# LP-IMP-P1_V3.net
KiCad netlist of a schematic drawn in EAGLE
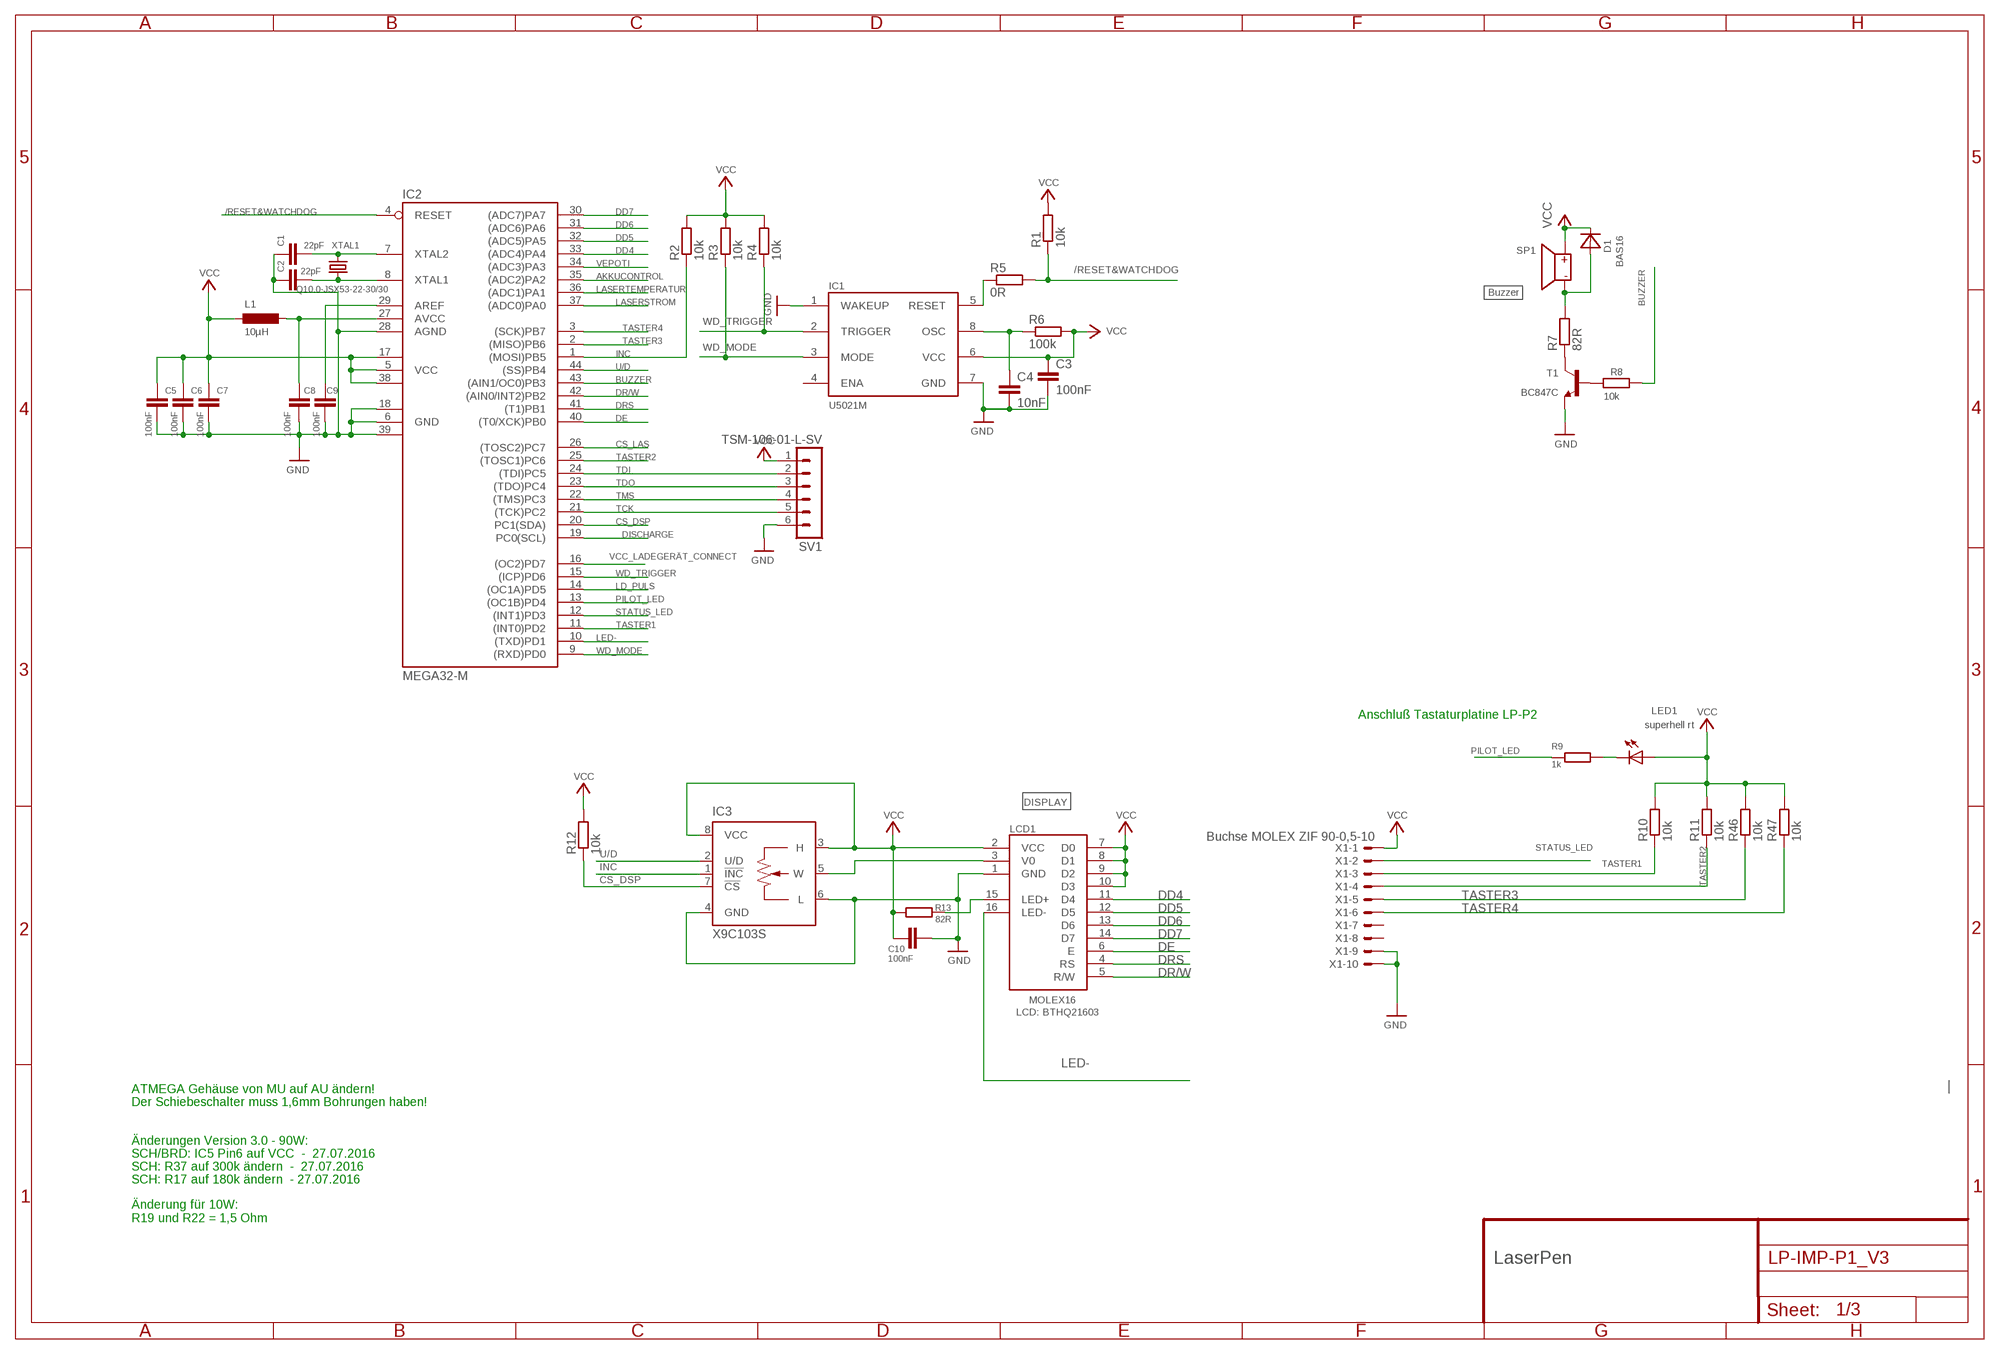
[diagram p0: schematic, sheet 1]
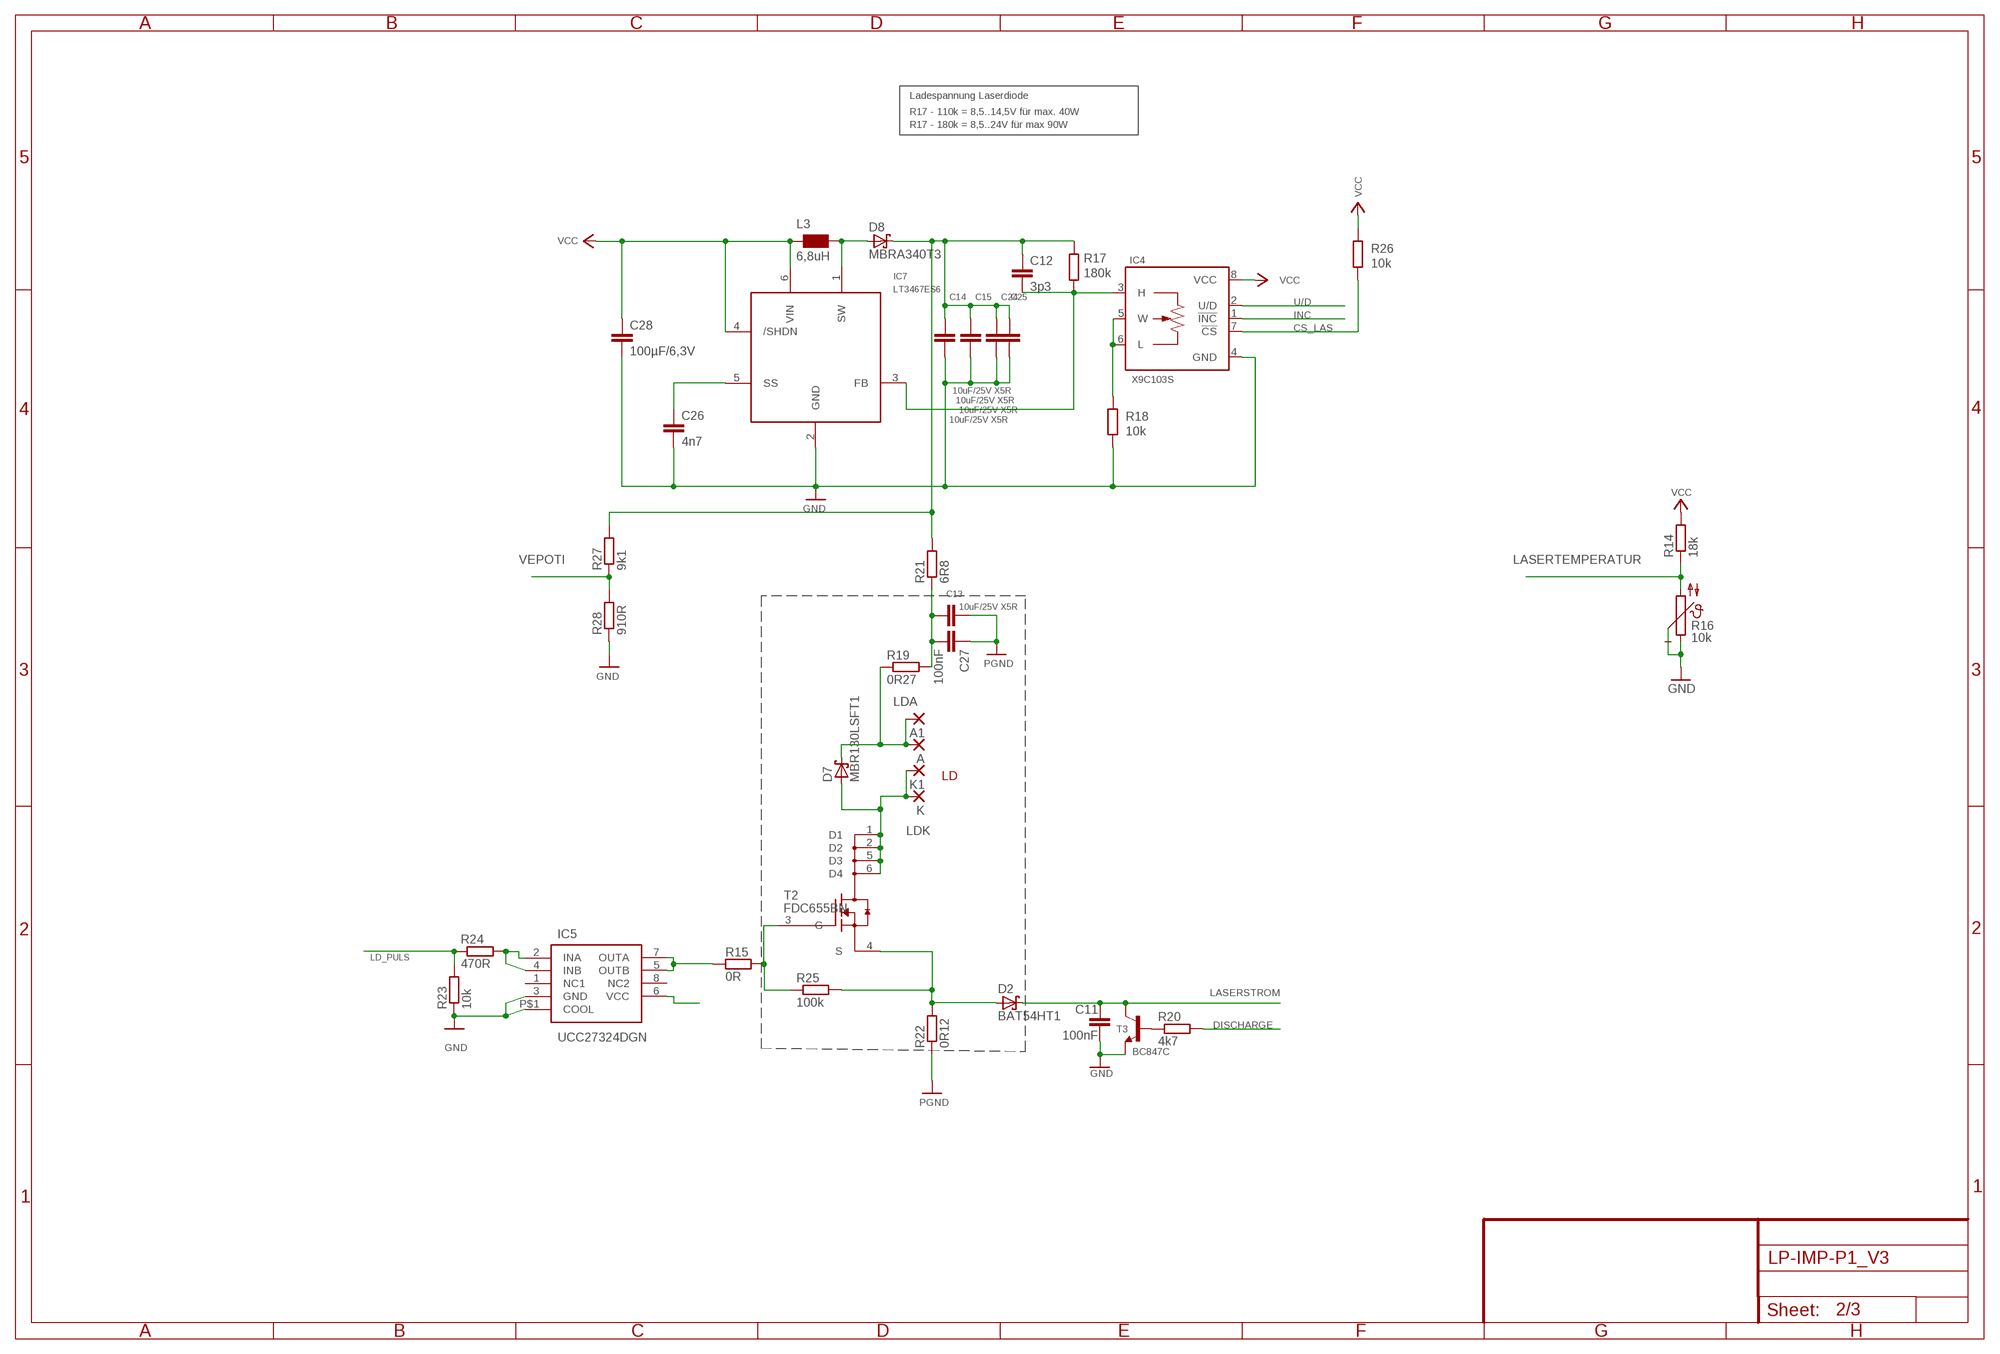
[diagram p1: schematic, sheet 2]
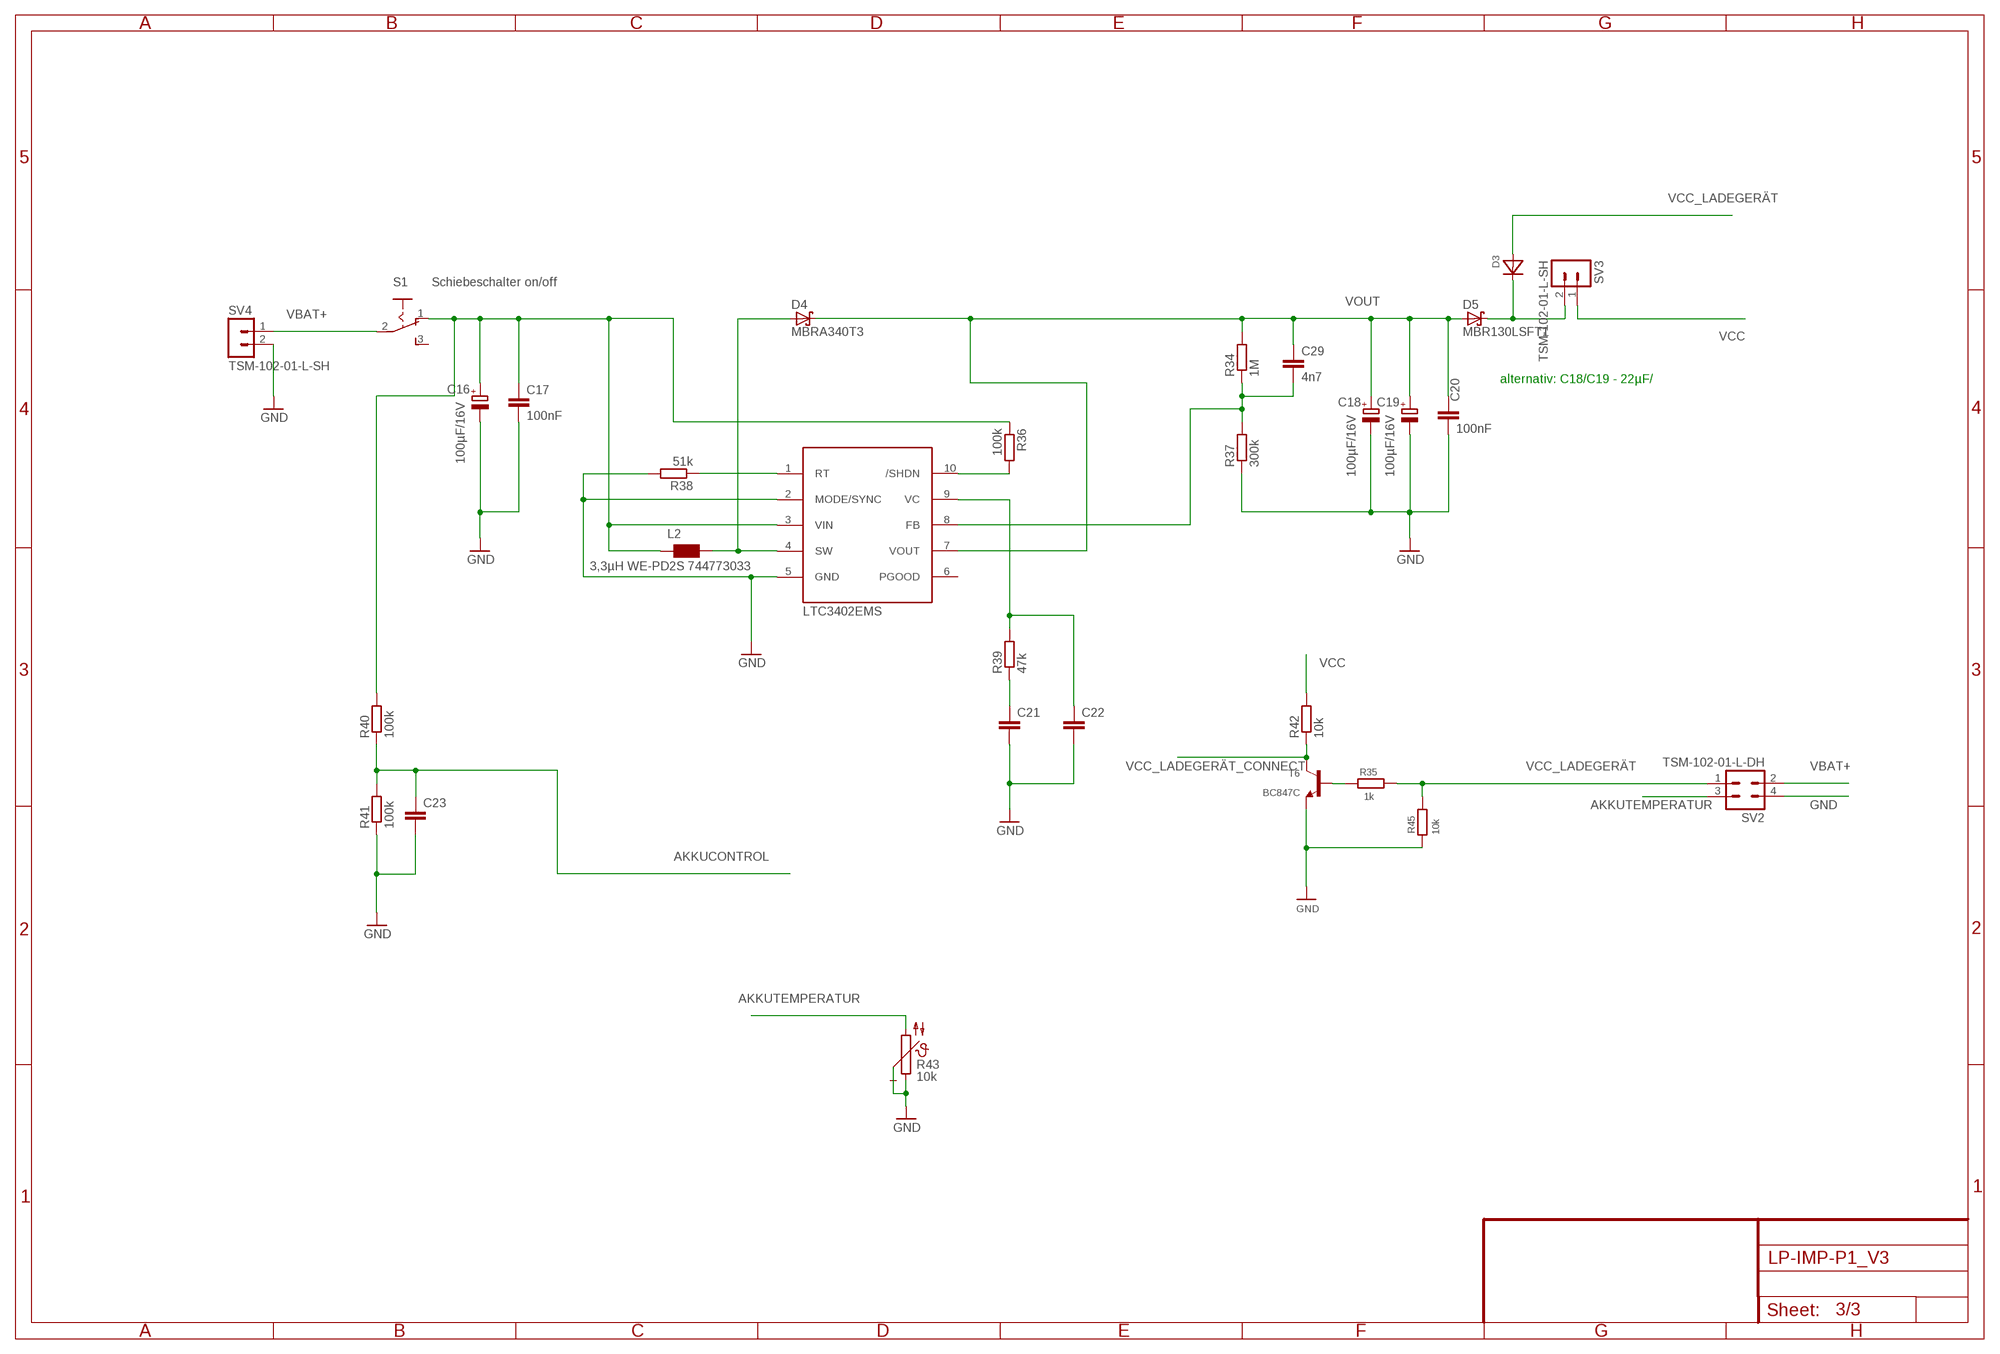
[diagram p2: schematic, sheet 3]

(export (version "E")
  (design (tool "Eeschema 10.0.6"))
  (components
    (comp (ref "C16")
      (value "100µF/16V")
      (footprint "eagle-import:SMC_D")
      (libsource (lib "eagle-import") (part "CPOL-EUSMCD"))
    )
    (comp (ref "C17")
      (value "100nF")
      (footprint "eagle-import:C0603K")
      (libsource (lib "eagle-import") (part "C-EUC0603K"))
    )
    (comp (ref "C18")
      (value "100µF/16V")
      (footprint "eagle-import:SMC_D")
      (libsource (lib "eagle-import") (part "CPOL-EUSMCD"))
    )
    (comp (ref "C19")
      (value "100µF/16V")
      (footprint "eagle-import:SMC_D")
      (libsource (lib "eagle-import") (part "CPOL-EUSMCD"))
    )
    (comp (ref "C20")
      (value "100nF")
      (footprint "eagle-import:C0603K")
      (libsource (lib "eagle-import") (part "C-EUC0603K"))
    )
    (comp (ref "C21")
      (value "1nF")
      (footprint "eagle-import:C0603K")
      (libsource (lib "eagle-import") (part "C-EUC0603K"))
    )
    (comp (ref "C22")
      (value "10pF")
      (footprint "eagle-import:C0603K")
      (libsource (lib "eagle-import") (part "C-EUC0603K"))
    )
    (comp (ref "C23")
      (value "100nF")
      (footprint "eagle-import:C0603K")
      (libsource (lib "eagle-import") (part "C-EUC0603K"))
    )
    (comp (ref "C29")
      (value "4n7")
      (footprint "eagle-import:C0603K")
      (libsource (lib "eagle-import") (part "C-EUC0603K"))
    )
    (comp (ref "D3")
      (value "BAS16")
      (footprint "eagle-import:DIODE_SOT23")
      (libsource (lib "eagle-import") (part "BAS16"))
    )
    (comp (ref "D4")
      (value "MBRA340T3")
      (footprint "eagle-import:SMA")
      (libsource (lib "eagle-import") (part "MBRA340T3"))
    )
    (comp (ref "D5")
      (value "MBR130LSFT1")
      (footprint "eagle-import:SOD-123LF")
      (libsource (lib "eagle-import") (part "MBR130LSFT1"))
    )
    (comp (ref "IC6")
      (value "LTC3402EMS")
      (footprint "eagle-import:MSOP-10")
      (libsource (lib "eagle-import") (part "LTC3402EMS"))
    )
    (comp (ref "L2")
      (value "3,3µH WE-PD2S 744773033")
      (footprint "eagle-import:WE-PD2_S")
      (libsource (lib "eagle-import") (part "wuerth-elektronik_EAGLE_v4_WE-PD2_S"))
    )
    (comp (ref "R34")
      (value "1M")
      (footprint "eagle-import:R0603")
      (libsource (lib "eagle-import") (part "R-EU_R0603"))
    )
    (comp (ref "R35")
      (value "1k")
      (footprint "eagle-import:R0603")
      (libsource (lib "eagle-import") (part "R-EU_R0603"))
    )
    (comp (ref "R36")
      (value "100k")
      (footprint "eagle-import:R0603")
      (libsource (lib "eagle-import") (part "R-EU_R0603"))
    )
    (comp (ref "R37")
      (value "300k")
      (footprint "eagle-import:R0603")
      (libsource (lib "eagle-import") (part "R-EU_R0603"))
    )
    (comp (ref "R38")
      (value "51k")
      (footprint "eagle-import:R0603")
      (libsource (lib "eagle-import") (part "R-EU_R0603"))
    )
    (comp (ref "R39")
      (value "47k")
      (footprint "eagle-import:R0603")
      (libsource (lib "eagle-import") (part "R-EU_R0603"))
    )
    (comp (ref "R40")
      (value "100k")
      (footprint "eagle-import:R0603")
      (libsource (lib "eagle-import") (part "R-EU_R0603"))
    )
    (comp (ref "R41")
      (value "100k")
      (footprint "eagle-import:R0603")
      (libsource (lib "eagle-import") (part "R-EU_R0603"))
    )
    (comp (ref "R42")
      (value "10k")
      (footprint "eagle-import:R0603")
      (libsource (lib "eagle-import") (part "R-EU_R0603"))
    )
    (comp (ref "R43")
      (value "10k")
      (footprint "eagle-import:R0805")
      (libsource (lib "eagle-import") (part "NTC640SMD0805"))
    )
    (comp (ref "R45")
      (value "10k")
      (footprint "eagle-import:R0603")
      (libsource (lib "eagle-import") (part "R-EU_R0603"))
    )
    (comp (ref "S1")
      (value "Schiebeschalter on/off")
      (footprint "eagle-import:255SB")
      (libsource (lib "eagle-import") (part "255SB"))
    )
    (comp (ref "SV2")
      (value "TSM-102-01-L-DH")
      (footprint "eagle-import:MA02-2-W-SMD")
      (libsource (lib "eagle-import") (part "MA02-2"))
    )
    (comp (ref "SV3")
      (value "TSM-102-01-L-SH")
      (footprint "eagle-import:MA02-1-W-SMD")
      (libsource (lib "eagle-import") (part "MA02-1W-SMD"))
    )
    (comp (ref "SV4")
      (value "TSM-102-01-L-SH")
      (footprint "eagle-import:MA02-1-W-SMD")
      (libsource (lib "eagle-import") (part "MA02-1W-SMD"))
    )
    (comp (ref "T6")
      (value "BC847C")
      (footprint "eagle-import:SOT23")
      (libsource (lib "eagle-import") (part "BC848"))
    )
    (comp (ref "A")
      (value "WIREPADSMD1,27-254")
      (footprint "eagle-import:SMD1,27-2,54")
      (libsource (lib "eagle-import") (part "WIREPADSMD1,27-254"))
    )
    (comp (ref "A1")
      (value "WIREPADSMD1,27-254")
      (footprint "eagle-import:SMD1,27-2,54")
      (libsource (lib "eagle-import") (part "WIREPADSMD1,27-254"))
    )
    (comp (ref "C11")
      (value "100nF")
      (footprint "eagle-import:C0603")
      (libsource (lib "eagle-import") (part "C-EUC0603"))
    )
    (comp (ref "C12")
      (value "3p3")
      (footprint "eagle-import:C0603")
      (libsource (lib "eagle-import") (part "C-EUC0603"))
    )
    (comp (ref "C13")
      (value "10uF/25V X5R")
      (footprint "eagle-import:C1210K")
      (libsource (lib "eagle-import") (part "C-EUC1210K"))
    )
    (comp (ref "C14")
      (value "10uF/25V X5R")
      (footprint "eagle-import:C1210K")
      (libsource (lib "eagle-import") (part "C-EUC1210K"))
    )
    (comp (ref "C15")
      (value "10uF/25V X5R")
      (footprint "eagle-import:C1210K")
      (libsource (lib "eagle-import") (part "C-EUC1210K"))
    )
    (comp (ref "C24")
      (value "10uF/25V X5R")
      (footprint "eagle-import:C1210K")
      (libsource (lib "eagle-import") (part "C-EUC1210K"))
    )
    (comp (ref "C25")
      (value "10uF/25V X5R")
      (footprint "eagle-import:C1210K")
      (libsource (lib "eagle-import") (part "C-EUC1210K"))
    )
    (comp (ref "C26")
      (value "4n7")
      (footprint "eagle-import:C0603K")
      (libsource (lib "eagle-import") (part "C-EUC0603K"))
    )
    (comp (ref "C27")
      (value "100nF")
      (footprint "eagle-import:C0603")
      (libsource (lib "eagle-import") (part "C-EUC0603"))
    )
    (comp (ref "C28")
      (value "100µF/6,3V")
      (footprint "eagle-import:C1210K")
      (libsource (lib "eagle-import") (part "C-EUC1210K"))
    )
    (comp (ref "D2")
      (value "BAT54HT1")
      (footprint "eagle-import:SOD-323")
      (libsource (lib "eagle-import") (part "BAT54HT1"))
    )
    (comp (ref "D7")
      (value "MBR130LSFT1")
      (footprint "eagle-import:SOD-123LF")
      (libsource (lib "eagle-import") (part "MBR130LSFT1"))
    )
    (comp (ref "D8")
      (value "MBRA340T3")
      (footprint "eagle-import:SMA")
      (libsource (lib "eagle-import") (part "pulslaser_MBRA340T3"))
    )
    (comp (ref "IC4")
      (value "X9C103S")
      (footprint "eagle-import:SOIC08")
      (libsource (lib "eagle-import") (part "X9C102S"))
    )
    (comp (ref "IC5")
      (value "UCC27324DGN")
      (footprint "eagle-import:R-PDSO-G8")
      (libsource (lib "eagle-import") (part "UCC27324DGN"))
    )
    (comp (ref "IC7")
      (value "LT3467ES6")
      (footprint "eagle-import:TSOT-23-6")
      (libsource (lib "eagle-import") (part "LT3467ES6"))
    )
    (comp (ref "K")
      (value "WIREPADSMD1,27-254")
      (footprint "eagle-import:SMD1,27-2,54")
      (libsource (lib "eagle-import") (part "WIREPADSMD1,27-254"))
    )
    (comp (ref "K1")
      (value "WIREPADSMD1,27-254")
      (footprint "eagle-import:SMD1,27-2,54")
      (libsource (lib "eagle-import") (part "WIREPADSMD1,27-254"))
    )
    (comp (ref "L3")
      (value "6,8uH")
      (footprint "eagle-import:WE-PD2_S")
      (libsource (lib "eagle-import") (part "WE-PD2_S"))
    )
    (comp (ref "R14")
      (value "18k")
      (footprint "eagle-import:R0603")
      (libsource (lib "eagle-import") (part "R-EU_R0603"))
    )
    (comp (ref "R15")
      (value "0R")
      (footprint "eagle-import:MINI_MELF-0204R")
      (libsource (lib "eagle-import") (part "R-EU_MELF0204R"))
    )
    (comp (ref "R16")
      (value "10k")
      (footprint "eagle-import:R0805")
      (libsource (lib "eagle-import") (part "NTC640SMD0805"))
    )
    (comp (ref "R17")
      (value "180k")
      (footprint "eagle-import:R0603")
      (libsource (lib "eagle-import") (part "R-EU_R0603"))
    )
    (comp (ref "R18")
      (value "10k")
      (footprint "eagle-import:R0603")
      (libsource (lib "eagle-import") (part "R-EU_R0603"))
    )
    (comp (ref "R19")
      (value "0R27")
      (footprint "eagle-import:MINI_MELF-0204R")
      (libsource (lib "eagle-import") (part "R-EU_MELF0204R"))
    )
    (comp (ref "R20")
      (value "4k7")
      (footprint "eagle-import:R0603")
      (libsource (lib "eagle-import") (part "R-EU_R0603"))
    )
    (comp (ref "R21")
      (value "6R8")
      (footprint "eagle-import:MINI_MELF-0204R")
      (libsource (lib "eagle-import") (part "R-EU_MELF0204R"))
    )
    (comp (ref "R22")
      (value "0R12")
      (footprint "eagle-import:MINI_MELF-0204R")
      (libsource (lib "eagle-import") (part "R-EU_MELF0204R"))
    )
    (comp (ref "R23")
      (value "10k")
      (footprint "eagle-import:R0603")
      (libsource (lib "eagle-import") (part "R-EU_R0603"))
    )
    (comp (ref "R24")
      (value "470R")
      (footprint "eagle-import:R0603")
      (libsource (lib "eagle-import") (part "R-EU_R0603"))
    )
    (comp (ref "R25")
      (value "100k")
      (footprint "eagle-import:R0603")
      (libsource (lib "eagle-import") (part "R-EU_R0603"))
    )
    (comp (ref "R26")
      (value "10k")
      (footprint "eagle-import:R0603")
      (libsource (lib "eagle-import") (part "R-EU_R0603"))
    )
    (comp (ref "R27")
      (value "9k1")
      (footprint "eagle-import:R0603")
      (libsource (lib "eagle-import") (part "R-EU_R0603"))
    )
    (comp (ref "R28")
      (value "910R")
      (footprint "eagle-import:R0603")
      (libsource (lib "eagle-import") (part "R-EU_R0603"))
    )
    (comp (ref "T2")
      (value "FDC655BN")
      (footprint "eagle-import:SUPERSOT-6")
      (libsource (lib "eagle-import") (part "FDC655BN"))
    )
    (comp (ref "T3")
      (value "BC847C")
      (footprint "eagle-import:SOT23-BEC")
      (libsource (lib "eagle-import") (part "BC849SMD"))
    )
    (comp (ref "C1")
      (value "22pF")
      (footprint "eagle-import:C0603")
      (libsource (lib "eagle-import") (part "C-EUC0603"))
    )
    (comp (ref "C2")
      (value "22pF")
      (footprint "eagle-import:C0603")
      (libsource (lib "eagle-import") (part "C-EUC0603"))
    )
    (comp (ref "C3")
      (value "100nF")
      (footprint "eagle-import:C0603")
      (libsource (lib "eagle-import") (part "C-EUC0603"))
    )
    (comp (ref "C4")
      (value "10nF")
      (footprint "eagle-import:C0603")
      (libsource (lib "eagle-import") (part "C-EUC0603"))
    )
    (comp (ref "C5")
      (value "100nF")
      (footprint "eagle-import:C0603")
      (libsource (lib "eagle-import") (part "C-EUC0603"))
    )
    (comp (ref "C6")
      (value "100nF")
      (footprint "eagle-import:C0603")
      (libsource (lib "eagle-import") (part "C-EUC0603"))
    )
    (comp (ref "C7")
      (value "100nF")
      (footprint "eagle-import:C0603")
      (libsource (lib "eagle-import") (part "C-EUC0603"))
    )
    (comp (ref "C8")
      (value "100nF")
      (footprint "eagle-import:C0603")
      (libsource (lib "eagle-import") (part "C-EUC0603"))
    )
    (comp (ref "C9")
      (value "100nF")
      (footprint "eagle-import:C0603")
      (libsource (lib "eagle-import") (part "C-EUC0603"))
    )
    (comp (ref "C10")
      (value "100nF")
      (footprint "eagle-import:C0603")
      (libsource (lib "eagle-import") (part "C-EUC0603"))
    )
    (comp (ref "D1")
      (value "BAS16")
      (footprint "eagle-import:DIODE_SOT23")
      (libsource (lib "eagle-import") (part "BAS16"))
    )
    (comp (ref "IC1")
      (value "U5021M")
      (footprint "eagle-import:SOIC8")
      (libsource (lib "eagle-import") (part "U5021M"))
    )
    (comp (ref "IC2")
      (value "MEGA32-M")
      (footprint "eagle-import:MLF44")
      (libsource (lib "eagle-import") (part "MEGA32-M"))
    )
    (comp (ref "IC3")
      (value "X9C103S")
      (footprint "eagle-import:SOIC08")
      (libsource (lib "eagle-import") (part "X9C102S"))
    )
    (comp (ref "L1")
      (value "10µH")
      (footprint "eagle-import:R1210")
      (libsource (lib "eagle-import") (part "L-EU"))
    )
    (comp (ref "LCD1")
      (value "MOLEX16")
      (footprint "eagle-import:MOLEX")
      (libsource (lib "eagle-import") (part "LCD1"))
    )
    (comp (ref "LED1")
      (value "superhell rt")
      (footprint "eagle-import:LED3MM")
      (libsource (lib "eagle-import") (part "LED3MM"))
    )
    (comp (ref "R1")
      (value "10k")
      (footprint "eagle-import:R0603")
      (libsource (lib "eagle-import") (part "R-EU_R0603"))
    )
    (comp (ref "R2")
      (value "10k")
      (footprint "eagle-import:R0603")
      (libsource (lib "eagle-import") (part "R-EU_R0603"))
    )
    (comp (ref "R3")
      (value "10k")
      (footprint "eagle-import:R0603")
      (libsource (lib "eagle-import") (part "R-EU_R0603"))
    )
    (comp (ref "R4")
      (value "10k")
      (footprint "eagle-import:R0603")
      (libsource (lib "eagle-import") (part "R-EU_R0603"))
    )
    (comp (ref "R5")
      (value "0R")
      (footprint "eagle-import:R0603")
      (libsource (lib "eagle-import") (part "R-EU_R0603"))
    )
    (comp (ref "R6")
      (value "100k")
      (footprint "eagle-import:R0603")
      (libsource (lib "eagle-import") (part "R-EU_R0603"))
    )
    (comp (ref "R7")
      (value "82R")
      (footprint "eagle-import:MINI_MELF-0204R")
      (libsource (lib "eagle-import") (part "R-EU_MELF0204R"))
    )
    (comp (ref "R8")
      (value "10k")
      (footprint "eagle-import:R0603")
      (libsource (lib "eagle-import") (part "R-EU_R0603"))
    )
    (comp (ref "R9")
      (value "1k")
      (footprint "eagle-import:R0603")
      (libsource (lib "eagle-import") (part "R-EU_R0603"))
    )
    (comp (ref "R10")
      (value "10k")
      (footprint "eagle-import:R0603")
      (libsource (lib "eagle-import") (part "R-EU_R0603"))
    )
    (comp (ref "R11")
      (value "10k")
      (footprint "eagle-import:R0603")
      (libsource (lib "eagle-import") (part "R-EU_R0603"))
    )
    (comp (ref "R12")
      (value "10k")
      (footprint "eagle-import:R0603")
      (libsource (lib "eagle-import") (part "R-EU_R0603"))
    )
    (comp (ref "R13")
      (value "82R")
      (footprint "eagle-import:MINI_MELF-0204R")
      (libsource (lib "eagle-import") (part "R-EU_MELF0204R"))
    )
    (comp (ref "R46")
      (value "10k")
      (footprint "eagle-import:R0603")
      (libsource (lib "eagle-import") (part "R-EU_R0603"))
    )
    (comp (ref "R47")
      (value "10k")
      (footprint "eagle-import:R0603")
      (libsource (lib "eagle-import") (part "R-EU_R0603"))
    )
    (comp (ref "SP1")
      (value "BUZZERS")
      (footprint "eagle-import:BUZZER")
      (libsource (lib "eagle-import") (part "BUZZERS"))
    )
    (comp (ref "SV1")
      (value "TSM-106-01-L-SV")
      (footprint "eagle-import:MA06-1-SMD")
      (libsource (lib "eagle-import") (part "MA06-1MA06-1-SMD"))
    )
    (comp (ref "T1")
      (value "BC847C")
      (footprint "eagle-import:SOT23")
      (libsource (lib "eagle-import") (part "BC848"))
    )
    (comp (ref "X1")
      (value "Buchse MOLEX ZIF 90-0,5-10")
      (footprint "eagle-import:52745-1090")
      (libsource (lib "eagle-import") (part "53?-10"))
    )
    (comp (ref "XTAL1")
      (value "Q10.0-JSX53-22-30/30")
      (footprint "eagle-import:JSX53")
      (libsource (lib "eagle-import") (part "JSX53"))
    )
  )
  (nets
    (net (code "1") (name "AKKUCONTROL") (class "Default")
      (node (ref "C23") (pin "1") (pinfunction "1_1") (pintype "passive"))
      (node (ref "IC2") (pin "35") (pinfunction "(ADC2)PA2_35") (pintype "bidirectional"))
      (node (ref "R40") (pin "1") (pinfunction "1_1") (pintype "passive"))
      (node (ref "R41") (pin "2") (pinfunction "2_2") (pintype "passive"))
    )
    (net (code "2") (name "AKKUTEMPERATUR") (class "Default")
      (node (ref "R43") (pin "2") (pinfunction "2_2") (pintype "passive"))
      (node (ref "SV2") (pin "3") (pinfunction "3_3") (pintype "passive"))
    )
    (net (code "3") (name "BUZZER") (class "Default")
      (node (ref "IC2") (pin "43") (pinfunction "(AIN1/OC0)PB3_43") (pintype "bidirectional"))
      (node (ref "R8") (pin "1") (pinfunction "1_1") (pintype "passive"))
    )
    (net (code "4") (name "CS_DSP") (class "Default")
      (node (ref "IC2") (pin "20") (pinfunction "PC1(SDA)_20") (pintype "bidirectional"))
      (node (ref "IC3") (pin "7") (pinfunction "~{CS}_7") (pintype "input"))
      (node (ref "R12") (pin "1") (pinfunction "1_1") (pintype "passive"))
    )
    (net (code "5") (name "CS_LAS") (class "Default")
      (node (ref "IC2") (pin "26") (pinfunction "(TOSC2)PC7_26") (pintype "bidirectional"))
      (node (ref "IC4") (pin "7") (pinfunction "~{CS}_7") (pintype "input"))
      (node (ref "R26") (pin "1") (pinfunction "1_1") (pintype "passive"))
    )
    (net (code "6") (name "DD4") (class "Default")
      (node (ref "IC2") (pin "33") (pinfunction "(ADC4)PA4_33") (pintype "bidirectional"))
      (node (ref "LCD1") (pin "11") (pinfunction "D4_11") (pintype "bidirectional"))
    )
    (net (code "7") (name "DD5") (class "Default")
      (node (ref "IC2") (pin "32") (pinfunction "(ADC5)PA5_32") (pintype "bidirectional"))
      (node (ref "LCD1") (pin "12") (pinfunction "D5_12") (pintype "bidirectional"))
    )
    (net (code "8") (name "DD6") (class "Default")
      (node (ref "IC2") (pin "31") (pinfunction "(ADC6)PA6_31") (pintype "bidirectional"))
      (node (ref "LCD1") (pin "13") (pinfunction "D6_13") (pintype "bidirectional"))
    )
    (net (code "9") (name "DD7") (class "Default")
      (node (ref "IC2") (pin "30") (pinfunction "(ADC7)PA7_30") (pintype "bidirectional"))
      (node (ref "LCD1") (pin "14") (pinfunction "D7_14") (pintype "bidirectional"))
    )
    (net (code "10") (name "DE") (class "Default")
      (node (ref "IC2") (pin "40") (pinfunction "(T0/XCK)PB0_40") (pintype "bidirectional"))
      (node (ref "LCD1") (pin "6") (pinfunction "E_6") (pintype "input"))
    )
    (net (code "11") (name "DISCHARGE") (class "Default")
      (node (ref "IC2") (pin "19") (pinfunction "PC0(SCL)_19") (pintype "bidirectional"))
      (node (ref "R20") (pin "2") (pinfunction "2_2") (pintype "passive"))
    )
    (net (code "12") (name "DRS") (class "Default")
      (node (ref "IC2") (pin "41") (pinfunction "(T1)PB1_41") (pintype "bidirectional"))
      (node (ref "LCD1") (pin "4") (pinfunction "RS_4") (pintype "input"))
    )
    (net (code "13") (name "DR{slash}W") (class "Default")
      (node (ref "IC2") (pin "42") (pinfunction "(AIN0/INT2)PB2_42") (pintype "bidirectional"))
      (node (ref "LCD1") (pin "5") (pinfunction "R/W_5") (pintype "input"))
    )
    (net (code "14") (name "GND") (class "Default")
      (node (ref "C1") (pin "1") (pinfunction "1_1") (pintype "passive"))
      (node (ref "C10") (pin "1") (pinfunction "1_1") (pintype "passive"))
      (node (ref "C11") (pin "2") (pinfunction "2_2") (pintype "passive"))
      (node (ref "C13") (pin "2") (pinfunction "2_2") (pintype "passive"))
      (node (ref "C14") (pin "2") (pinfunction "2_2") (pintype "passive"))
      (node (ref "C15") (pin "2") (pinfunction "2_2") (pintype "passive"))
      (node (ref "C16") (pin "-") (pinfunction "-_-") (pintype "passive"))
      (node (ref "C17") (pin "2") (pinfunction "2_2") (pintype "passive"))
      (node (ref "C18") (pin "-") (pinfunction "-_-") (pintype "passive"))
      (node (ref "C19") (pin "-") (pinfunction "-_-") (pintype "passive"))
      (node (ref "C2") (pin "1") (pinfunction "1_1") (pintype "passive"))
      (node (ref "C20") (pin "2") (pinfunction "2_2") (pintype "passive"))
      (node (ref "C21") (pin "2") (pinfunction "2_2") (pintype "passive"))
      (node (ref "C22") (pin "2") (pinfunction "2_2") (pintype "passive"))
      (node (ref "C23") (pin "2") (pinfunction "2_2") (pintype "passive"))
      (node (ref "C24") (pin "2") (pinfunction "2_2") (pintype "passive"))
      (node (ref "C25") (pin "2") (pinfunction "2_2") (pintype "passive"))
      (node (ref "C26") (pin "2") (pinfunction "2_2") (pintype "passive"))
      (node (ref "C27") (pin "1") (pinfunction "1_1") (pintype "passive"))
      (node (ref "C28") (pin "2") (pinfunction "2_2") (pintype "passive"))
      (node (ref "C3") (pin "2") (pinfunction "2_2") (pintype "passive"))
      (node (ref "C4") (pin "2") (pinfunction "2_2") (pintype "passive"))
      (node (ref "C5") (pin "2") (pinfunction "2_2") (pintype "passive"))
      (node (ref "C6") (pin "2") (pinfunction "2_2") (pintype "passive"))
      (node (ref "C7") (pin "2") (pinfunction "2_2") (pintype "passive"))
      (node (ref "C8") (pin "2") (pinfunction "2_2") (pintype "passive"))
      (node (ref "C9") (pin "2") (pinfunction "2_2") (pintype "passive"))
      (node (ref "IC1") (pin "1") (pinfunction "WAKEUP_1") (pintype "bidirectional"))
      (node (ref "IC1") (pin "7") (pinfunction "GND_7") (pintype "bidirectional"))
      (node (ref "IC2") (pin "18") (pinfunction "GND1_18") (pintype "power_in"))
      (node (ref "IC2") (pin "28") (pinfunction "AGND_28") (pintype "power_in"))
      (node (ref "IC2") (pin "39") (pinfunction "GND2_39") (pintype "power_in"))
      (node (ref "IC2") (pin "6") (pinfunction "GND_6") (pintype "power_in"))
      (node (ref "IC3") (pin "4") (pinfunction "GND_4") (pintype "power_in"))
      (node (ref "IC3") (pin "6") (pinfunction "L_6") (pintype "passive"))
      (node (ref "IC4") (pin "4") (pinfunction "GND_4") (pintype "power_in"))
      (node (ref "IC5") (pin "3") (pinfunction "GND_3") (pintype "power_in"))
      (node (ref "IC5") (pin "P$1") (pinfunction "COOL_P$1") (pintype "passive"))
      (node (ref "IC6") (pin "2") (pinfunction "MODE/SYNC_2") (pintype "input"))
      (node (ref "IC6") (pin "5") (pinfunction "GND_5") (pintype "power_in"))
      (node (ref "IC7") (pin "2") (pinfunction "GND_2") (pintype "power_in"))
      (node (ref "LCD1") (pin "1") (pinfunction "GND_1") (pintype "power_in"))
      (node (ref "R16") (pin "1") (pinfunction "1_1") (pintype "passive"))
      (node (ref "R18") (pin "1") (pinfunction "1_1") (pintype "passive"))
      (node (ref "R22") (pin "1") (pinfunction "1_1") (pintype "passive"))
      (node (ref "R23") (pin "1") (pinfunction "1_1") (pintype "passive"))
      (node (ref "R28") (pin "1") (pinfunction "1_1") (pintype "passive"))
      (node (ref "R37") (pin "1") (pinfunction "1_1") (pintype "passive"))
      (node (ref "R38") (pin "2") (pinfunction "2_2") (pintype "passive"))
      (node (ref "R41") (pin "1") (pinfunction "1_1") (pintype "passive"))
      (node (ref "R43") (pin "1") (pinfunction "1_1") (pintype "passive"))
      (node (ref "R45") (pin "2") (pinfunction "2_2") (pintype "passive"))
      (node (ref "SV1") (pin "6") (pinfunction "6_6") (pintype "passive"))
      (node (ref "SV2") (pin "4") (pinfunction "4_4") (pintype "passive"))
      (node (ref "SV4") (pin "2") (pinfunction "2_2") (pintype "passive"))
      (node (ref "T1") (pin "2") (pinfunction "E_2") (pintype "passive"))
      (node (ref "T3") (pin "E") (pinfunction "E_E") (pintype "passive"))
      (node (ref "T6") (pin "2") (pinfunction "E_2") (pintype "passive"))
      (node (ref "X1") (pin "10") (pinfunction "S_10") (pintype "passive"))
      (node (ref "X1") (pin "9") (pinfunction "S_9") (pintype "passive"))
    )
    (net (code "15") (name "INC") (class "Default")
      (node (ref "IC2") (pin "1") (pinfunction "(MOSI)PB5_1") (pintype "bidirectional"))
      (node (ref "IC3") (pin "1") (pinfunction "~{INC}_1") (pintype "input"))
      (node (ref "IC4") (pin "1") (pinfunction "~{INC}_1") (pintype "input"))
      (node (ref "R2") (pin "1") (pinfunction "1_1") (pintype "passive"))
    )
    (net (code "16") (name "LASERSTROM") (class "Default")
      (node (ref "C11") (pin "1") (pinfunction "1_1") (pintype "passive"))
      (node (ref "D2") (pin "C") (pinfunction "C_C") (pintype "passive"))
      (node (ref "IC2") (pin "37") (pinfunction "(ADC0)PA0_37") (pintype "bidirectional"))
      (node (ref "T3") (pin "C") (pinfunction "C_C") (pintype "passive"))
    )
    (net (code "17") (name "LASERTEMPERATUR") (class "Default")
      (node (ref "IC2") (pin "36") (pinfunction "(ADC1)PA1_36") (pintype "bidirectional"))
      (node (ref "R14") (pin "1") (pinfunction "1_1") (pintype "passive"))
      (node (ref "R16") (pin "2") (pinfunction "2_2") (pintype "passive"))
    )
    (net (code "18") (name "LDA") (class "Default")
      (node (ref "A") (pin "1") (pinfunction "P_1") (pintype "passive"))
      (node (ref "A1") (pin "1") (pinfunction "P_1") (pintype "passive"))
      (node (ref "D7") (pin "C") (pinfunction "C_C") (pintype "passive"))
      (node (ref "R19") (pin "1") (pinfunction "1_1") (pintype "passive"))
    )
    (net (code "19") (name "LDK") (class "Default")
      (node (ref "D7") (pin "A") (pinfunction "A_A") (pintype "passive"))
      (node (ref "K") (pin "1") (pinfunction "P_1") (pintype "passive"))
      (node (ref "K1") (pin "1") (pinfunction "P_1") (pintype "passive"))
      (node (ref "T2") (pin "1") (pinfunction "D1_1") (pintype "passive"))
      (node (ref "T2") (pin "2") (pinfunction "D2_2") (pintype "passive"))
      (node (ref "T2") (pin "5") (pinfunction "D3_5") (pintype "passive"))
      (node (ref "T2") (pin "6") (pinfunction "D4_6") (pintype "passive"))
    )
    (net (code "20") (name "LD_PULS") (class "Default")
      (node (ref "IC2") (pin "14") (pinfunction "(OC1A)PD5_14") (pintype "bidirectional"))
      (node (ref "R23") (pin "2") (pinfunction "2_2") (pintype "passive"))
      (node (ref "R24") (pin "1") (pinfunction "1_1") (pintype "passive"))
    )
    (net (code "21") (name "LED-") (class "Default")
      (node (ref "IC2") (pin "10") (pinfunction "(TXD)PD1_10") (pintype "bidirectional"))
      (node (ref "LCD1") (pin "16") (pinfunction "LED-_16") (pintype "power_in"))
    )
    (net (code "22") (name "Net-(C12-Pad1)") (class "Default")
      (node (ref "C12") (pin "1") (pinfunction "1_1") (pintype "passive"))
      (node (ref "C14") (pin "1") (pinfunction "1_1") (pintype "passive"))
      (node (ref "C15") (pin "1") (pinfunction "1_1") (pintype "passive"))
      (node (ref "C24") (pin "1") (pinfunction "1_1") (pintype "passive"))
      (node (ref "C25") (pin "1") (pinfunction "1_1") (pintype "passive"))
      (node (ref "D8") (pin "C") (pinfunction "C_C") (pintype "passive"))
      (node (ref "R17") (pin "2") (pinfunction "2_2") (pintype "passive"))
      (node (ref "R21") (pin "2") (pinfunction "2_2") (pintype "passive"))
      (node (ref "R27") (pin "2") (pinfunction "2_2") (pintype "passive"))
    )
    (net (code "23") (name "Net-(C13-Pad1)") (class "Default")
      (node (ref "C13") (pin "1") (pinfunction "1_1") (pintype "passive"))
      (node (ref "C27") (pin "2") (pinfunction "2_2") (pintype "passive"))
      (node (ref "R19") (pin "2") (pinfunction "2_2") (pintype "passive"))
      (node (ref "R21") (pin "1") (pinfunction "1_1") (pintype "passive"))
    )
    (net (code "24") (name "Net-(C21-Pad1)") (class "Default")
      (node (ref "C21") (pin "1") (pinfunction "1_1") (pintype "passive"))
      (node (ref "R39") (pin "1") (pinfunction "1_1") (pintype "passive"))
    )
    (net (code "25") (name "Net-(D1-A)") (class "Default")
      (node (ref "D1") (pin "1") (pinfunction "A_1") (pintype "passive"))
      (node (ref "R7") (pin "2") (pinfunction "2_2") (pintype "passive"))
      (node (ref "SP1") (pin "-") (pinfunction "-_-") (pintype "passive"))
    )
    (net (code "26") (name "Net-(D3-C)") (class "Default")
      (node (ref "D3") (pin "3") (pinfunction "C_3") (pintype "passive"))
      (node (ref "D5") (pin "C") (pinfunction "C_C") (pintype "passive"))
      (node (ref "SV3") (pin "2") (pinfunction "2_2") (pintype "passive"))
    )
    (net (code "27") (name "Net-(IC1-OSC)") (class "Default")
      (node (ref "C4") (pin "1") (pinfunction "1_1") (pintype "passive"))
      (node (ref "IC1") (pin "8") (pinfunction "OSC_8") (pintype "bidirectional"))
      (node (ref "R6") (pin "1") (pinfunction "1_1") (pintype "passive"))
    )
    (net (code "28") (name "Net-(IC1-RESET)") (class "Default")
      (node (ref "IC1") (pin "5") (pinfunction "RESET_5") (pintype "bidirectional"))
      (node (ref "R5") (pin "1") (pinfunction "1_1") (pintype "passive"))
    )
    (net (code "29") (name "Net-(IC2-AREF)") (class "Default")
      (node (ref "C9") (pin "1") (pinfunction "1_1") (pintype "passive"))
      (node (ref "IC2") (pin "29") (pinfunction "AREF_29") (pintype "power_in"))
    )
    (net (code "30") (name "Net-(IC2-AVCC)") (class "Default")
      (node (ref "C8") (pin "1") (pinfunction "1_1") (pintype "passive"))
      (node (ref "IC2") (pin "27") (pinfunction "AVCC_27") (pintype "power_in"))
      (node (ref "L1") (pin "1") (pinfunction "1_1") (pintype "passive"))
    )
    (net (code "31") (name "Net-(IC2-XTAL1)") (class "Default")
      (node (ref "C2") (pin "2") (pinfunction "2_2") (pintype "passive"))
      (node (ref "IC2") (pin "8") (pinfunction "XTAL1_8") (pintype "bidirectional"))
      (node (ref "XTAL1") (pin "1") (pinfunction "1_1") (pintype "passive"))
    )
    (net (code "32") (name "Net-(IC2-XTAL2)") (class "Default")
      (node (ref "C1") (pin "2") (pinfunction "2_2") (pintype "passive"))
      (node (ref "IC2") (pin "7") (pinfunction "XTAL2_7") (pintype "bidirectional"))
      (node (ref "XTAL1") (pin "3") (pinfunction "2_3") (pintype "passive"))
    )
    (net (code "33") (name "Net-(IC3-W)") (class "Default")
      (node (ref "IC3") (pin "5") (pinfunction "W_5") (pintype "passive"))
      (node (ref "LCD1") (pin "3") (pinfunction "V0_3") (pintype "power_in"))
    )
    (net (code "34") (name "Net-(IC4-H)") (class "Default")
      (node (ref "C12") (pin "2") (pinfunction "2_2") (pintype "passive"))
      (node (ref "IC4") (pin "3") (pinfunction "H_3") (pintype "passive"))
      (node (ref "IC7") (pin "3") (pinfunction "FB_3") (pintype "passive"))
      (node (ref "R17") (pin "1") (pinfunction "1_1") (pintype "passive"))
    )
    (net (code "35") (name "Net-(IC4-L)") (class "Default")
      (node (ref "IC4") (pin "5") (pinfunction "W_5") (pintype "passive"))
      (node (ref "IC4") (pin "6") (pinfunction "L_6") (pintype "passive"))
      (node (ref "R18") (pin "2") (pinfunction "2_2") (pintype "passive"))
    )
    (net (code "36") (name "Net-(IC5-INA)") (class "Default")
      (node (ref "IC5") (pin "2") (pinfunction "INA_2") (pintype "input"))
      (node (ref "IC5") (pin "4") (pinfunction "INB_4") (pintype "input"))
      (node (ref "R24") (pin "2") (pinfunction "2_2") (pintype "passive"))
    )
    (net (code "37") (name "Net-(IC5-OUTA)") (class "Default")
      (node (ref "IC5") (pin "5") (pinfunction "OUTB_5") (pintype "output"))
      (node (ref "IC5") (pin "7") (pinfunction "OUTA_7") (pintype "output"))
      (node (ref "R15") (pin "1") (pinfunction "1_1") (pintype "passive"))
    )
    (net (code "38") (name "Net-(IC6-FB)") (class "Default")
      (node (ref "C29") (pin "2") (pinfunction "2_2") (pintype "passive"))
      (node (ref "IC6") (pin "8") (pinfunction "FB_8") (pintype "passive"))
      (node (ref "R34") (pin "1") (pinfunction "1_1") (pintype "passive"))
      (node (ref "R37") (pin "2") (pinfunction "2_2") (pintype "passive"))
    )
    (net (code "39") (name "Net-(IC6-RT)") (class "Default")
      (node (ref "IC6") (pin "1") (pinfunction "RT_1") (pintype "passive"))
      (node (ref "R38") (pin "1") (pinfunction "1_1") (pintype "passive"))
    )
    (net (code "40") (name "Net-(IC6-SW)") (class "Default")
      (node (ref "D4") (pin "A") (pinfunction "A_A") (pintype "passive"))
      (node (ref "IC6") (pin "4") (pinfunction "SW_4") (pintype "passive"))
      (node (ref "L2") (pin "1") (pinfunction "2_1") (pintype "passive"))
    )
    (net (code "41") (name "Net-(IC6-VC)") (class "Default")
      (node (ref "C22") (pin "1") (pinfunction "1_1") (pintype "passive"))
      (node (ref "IC6") (pin "9") (pinfunction "VC_9") (pintype "passive"))
      (node (ref "R39") (pin "2") (pinfunction "2_2") (pintype "passive"))
    )
    (net (code "42") (name "Net-(IC6-VIN)") (class "Default")
      (node (ref "C16") (pin "+") (pinfunction "+_+") (pintype "passive"))
      (node (ref "C17") (pin "1") (pinfunction "1_1") (pintype "passive"))
      (node (ref "IC6") (pin "3") (pinfunction "VIN_3") (pintype "power_in"))
      (node (ref "L2") (pin "2") (pinfunction "1_2") (pintype "passive"))
      (node (ref "R36") (pin "1") (pinfunction "1_1") (pintype "passive"))
      (node (ref "R40") (pin "2") (pinfunction "2_2") (pintype "passive"))
      (node (ref "S1") (pin "1") (pinfunction "O_1") (pintype "passive"))
    )
    (net (code "43") (name "Net-(IC6-{slash}SHDN)") (class "Default")
      (node (ref "IC6") (pin "10") (pinfunction "/SHDN_10") (pintype "input"))
      (node (ref "R36") (pin "2") (pinfunction "2_2") (pintype "passive"))
    )
    (net (code "44") (name "Net-(IC7-SS)") (class "Default")
      (node (ref "C26") (pin "1") (pinfunction "1_1") (pintype "passive"))
      (node (ref "IC7") (pin "5") (pinfunction "SS_5") (pintype "passive"))
    )
    (net (code "45") (name "Net-(IC7-SW)") (class "Default")
      (node (ref "D8") (pin "A") (pinfunction "A_A") (pintype "passive"))
      (node (ref "IC7") (pin "1") (pinfunction "SW_1") (pintype "passive"))
      (node (ref "L3") (pin "1") (pinfunction "2_1") (pintype "passive"))
    )
    (net (code "46") (name "Net-(LCD1-LED+)") (class "Default")
      (node (ref "LCD1") (pin "15") (pinfunction "LED+_15") (pintype "power_in"))
      (node (ref "R13") (pin "2") (pinfunction "2_2") (pintype "passive"))
    )
    (net (code "47") (name "Net-(LED1-C)") (class "Default")
      (node (ref "LED1") (pin "K") (pinfunction "C_K") (pintype "passive"))
      (node (ref "R9") (pin "2") (pinfunction "2_2") (pintype "passive"))
    )
    (net (code "48") (name "Net-(R20-Pad1)") (class "Default")
      (node (ref "R20") (pin "1") (pinfunction "1_1") (pintype "passive"))
      (node (ref "T3") (pin "B") (pinfunction "B_B") (pintype "passive"))
    )
    (net (code "49") (name "Net-(T1-B)") (class "Default")
      (node (ref "R8") (pin "2") (pinfunction "2_2") (pintype "passive"))
      (node (ref "T1") (pin "1") (pinfunction "B_1") (pintype "passive"))
    )
    (net (code "50") (name "Net-(T1-C)") (class "Default")
      (node (ref "R7") (pin "1") (pinfunction "1_1") (pintype "passive"))
      (node (ref "T1") (pin "3") (pinfunction "C_3") (pintype "passive"))
    )
    (net (code "51") (name "Net-(T2-G)") (class "Default")
      (node (ref "R15") (pin "2") (pinfunction "2_2") (pintype "passive"))
      (node (ref "R25") (pin "1") (pinfunction "1_1") (pintype "passive"))
      (node (ref "T2") (pin "3") (pinfunction "G_3") (pintype "passive"))
    )
    (net (code "52") (name "Net-(T2-S)") (class "Default")
      (node (ref "D2") (pin "A") (pinfunction "A_A") (pintype "passive"))
      (node (ref "R22") (pin "2") (pinfunction "2_2") (pintype "passive"))
      (node (ref "R25") (pin "2") (pinfunction "2_2") (pintype "passive"))
      (node (ref "T2") (pin "4") (pinfunction "S_4") (pintype "passive"))
    )
    (net (code "53") (name "Net-(T6-B)") (class "Default")
      (node (ref "R35") (pin "2") (pinfunction "2_2") (pintype "passive"))
      (node (ref "T6") (pin "1") (pinfunction "B_1") (pintype "passive"))
    )
    (net (code "54") (name "PILOT_LED") (class "Default")
      (node (ref "IC2") (pin "13") (pinfunction "(OC1B)PD4_13") (pintype "bidirectional"))
      (node (ref "R9") (pin "1") (pinfunction "1_1") (pintype "passive"))
    )
    (net (code "55") (name "STATUS_LED") (class "Default")
      (node (ref "IC2") (pin "12") (pinfunction "(INT1)PD3_12") (pintype "bidirectional"))
      (node (ref "X1") (pin "2") (pinfunction "S_2") (pintype "passive"))
    )
    (net (code "56") (name "TASTER1") (class "Default")
      (node (ref "IC2") (pin "11") (pinfunction "(INT0)PD2_11") (pintype "bidirectional"))
      (node (ref "R10") (pin "1") (pinfunction "1_1") (pintype "passive"))
      (node (ref "X1") (pin "3") (pinfunction "S_3") (pintype "passive"))
    )
    (net (code "57") (name "TASTER2") (class "Default")
      (node (ref "IC2") (pin "25") (pinfunction "(TOSC1)PC6_25") (pintype "bidirectional"))
      (node (ref "R11") (pin "1") (pinfunction "1_1") (pintype "passive"))
      (node (ref "X1") (pin "4") (pinfunction "S_4") (pintype "passive"))
    )
    (net (code "58") (name "TASTER3") (class "Default")
      (node (ref "IC2") (pin "2") (pinfunction "(MISO)PB6_2") (pintype "bidirectional"))
      (node (ref "R46") (pin "1") (pinfunction "1_1") (pintype "passive"))
      (node (ref "X1") (pin "5") (pinfunction "S_5") (pintype "passive"))
    )
    (net (code "59") (name "TASTER4") (class "Default")
      (node (ref "IC2") (pin "3") (pinfunction "(SCK)PB7_3") (pintype "bidirectional"))
      (node (ref "R47") (pin "1") (pinfunction "1_1") (pintype "passive"))
      (node (ref "X1") (pin "6") (pinfunction "S_6") (pintype "passive"))
    )
    (net (code "60") (name "TCK") (class "Default")
      (node (ref "IC2") (pin "21") (pinfunction "(TCK)PC2_21") (pintype "bidirectional"))
      (node (ref "SV1") (pin "5") (pinfunction "5_5") (pintype "passive"))
    )
    (net (code "61") (name "TDI") (class "Default")
      (node (ref "IC2") (pin "24") (pinfunction "(TDI)PC5_24") (pintype "bidirectional"))
      (node (ref "SV1") (pin "2") (pinfunction "2_2") (pintype "passive"))
    )
    (net (code "62") (name "TDO") (class "Default")
      (node (ref "IC2") (pin "23") (pinfunction "(TDO)PC4_23") (pintype "bidirectional"))
      (node (ref "SV1") (pin "3") (pinfunction "3_3") (pintype "passive"))
    )
    (net (code "63") (name "TMS") (class "Default")
      (node (ref "IC2") (pin "22") (pinfunction "(TMS)PC3_22") (pintype "bidirectional"))
      (node (ref "SV1") (pin "4") (pinfunction "4_4") (pintype "passive"))
    )
    (net (code "64") (name "U{slash}D") (class "Default")
      (node (ref "IC2") (pin "44") (pinfunction "(SS)PB4_44") (pintype "bidirectional"))
      (node (ref "IC3") (pin "2") (pinfunction "U/D_2") (pintype "input"))
      (node (ref "IC4") (pin "2") (pinfunction "U/D_2") (pintype "input"))
    )
    (net (code "65") (name "VBAT+") (class "Default")
      (node (ref "S1") (pin "2") (pinfunction "P_2") (pintype "passive"))
      (node (ref "SV2") (pin "2") (pinfunction "2_2") (pintype "passive"))
      (node (ref "SV4") (pin "1") (pinfunction "1_1") (pintype "passive"))
    )
    (net (code "66") (name "VCC") (class "Default")
      (node (ref "C10") (pin "2") (pinfunction "2_2") (pintype "passive"))
      (node (ref "C28") (pin "1") (pinfunction "1_1") (pintype "passive"))
      (node (ref "C3") (pin "1") (pinfunction "1_1") (pintype "passive"))
      (node (ref "C5") (pin "1") (pinfunction "1_1") (pintype "passive"))
      (node (ref "C6") (pin "1") (pinfunction "1_1") (pintype "passive"))
      (node (ref "C7") (pin "1") (pinfunction "1_1") (pintype "passive"))
      (node (ref "D1") (pin "3") (pinfunction "C_3") (pintype "passive"))
      (node (ref "IC1") (pin "6") (pinfunction "VCC_6") (pintype "bidirectional"))
      (node (ref "IC2") (pin "17") (pinfunction "VCC1_17") (pintype "power_in"))
      (node (ref "IC2") (pin "38") (pinfunction "VCC2_38") (pintype "power_in"))
      (node (ref "IC2") (pin "5") (pinfunction "VCC_5") (pintype "power_in"))
      (node (ref "IC3") (pin "3") (pinfunction "H_3") (pintype "passive"))
      (node (ref "IC3") (pin "8") (pinfunction "VCC_8") (pintype "power_in"))
      (node (ref "IC4") (pin "8") (pinfunction "VCC_8") (pintype "power_in"))
      (node (ref "IC5") (pin "6") (pinfunction "VCC_6") (pintype "power_in"))
      (node (ref "IC7") (pin "4") (pinfunction "/SHDN_4") (pintype "input"))
      (node (ref "IC7") (pin "6") (pinfunction "VIN_6") (pintype "power_in"))
      (node (ref "L1") (pin "2") (pinfunction "2_2") (pintype "passive"))
      (node (ref "L3") (pin "2") (pinfunction "1_2") (pintype "passive"))
      (node (ref "LCD1") (pin "10") (pinfunction "D3_10") (pintype "bidirectional"))
      (node (ref "LCD1") (pin "2") (pinfunction "VCC_2") (pintype "power_in"))
      (node (ref "LCD1") (pin "7") (pinfunction "D0_7") (pintype "bidirectional"))
      (node (ref "LCD1") (pin "8") (pinfunction "D1_8") (pintype "bidirectional"))
      (node (ref "LCD1") (pin "9") (pinfunction "D2_9") (pintype "bidirectional"))
      (node (ref "LED1") (pin "A") (pinfunction "A_A") (pintype "passive"))
      (node (ref "R1") (pin "2") (pinfunction "2_2") (pintype "passive"))
      (node (ref "R10") (pin "2") (pinfunction "2_2") (pintype "passive"))
      (node (ref "R11") (pin "2") (pinfunction "2_2") (pintype "passive"))
      (node (ref "R12") (pin "2") (pinfunction "2_2") (pintype "passive"))
      (node (ref "R13") (pin "1") (pinfunction "1_1") (pintype "passive"))
      (node (ref "R14") (pin "2") (pinfunction "2_2") (pintype "passive"))
      (node (ref "R2") (pin "2") (pinfunction "2_2") (pintype "passive"))
      (node (ref "R26") (pin "2") (pinfunction "2_2") (pintype "passive"))
      (node (ref "R3") (pin "2") (pinfunction "2_2") (pintype "passive"))
      (node (ref "R4") (pin "2") (pinfunction "2_2") (pintype "passive"))
      (node (ref "R42") (pin "2") (pinfunction "2_2") (pintype "passive"))
      (node (ref "R46") (pin "2") (pinfunction "2_2") (pintype "passive"))
      (node (ref "R47") (pin "2") (pinfunction "2_2") (pintype "passive"))
      (node (ref "R6") (pin "2") (pinfunction "2_2") (pintype "passive"))
      (node (ref "SP1") (pin "+") (pinfunction "+_+") (pintype "passive"))
      (node (ref "SV1") (pin "1") (pinfunction "1_1") (pintype "passive"))
      (node (ref "SV3") (pin "1") (pinfunction "1_1") (pintype "passive"))
      (node (ref "X1") (pin "1") (pinfunction "S_1") (pintype "passive"))
    )
    (net (code "67") (name "VCC_LADEGERÄT") (class "Default")
      (node (ref "D3") (pin "1") (pinfunction "A_1") (pintype "passive"))
      (node (ref "R35") (pin "1") (pinfunction "1_1") (pintype "passive"))
      (node (ref "R45") (pin "1") (pinfunction "1_1") (pintype "passive"))
      (node (ref "SV2") (pin "1") (pinfunction "1_1") (pintype "passive"))
    )
    (net (code "68") (name "VCC_LADEGERÄT_CONNECT") (class "Default")
      (node (ref "IC2") (pin "16") (pinfunction "(OC2)PD7_16") (pintype "bidirectional"))
      (node (ref "R42") (pin "1") (pinfunction "1_1") (pintype "passive"))
      (node (ref "T6") (pin "3") (pinfunction "C_3") (pintype "passive"))
    )
    (net (code "69") (name "VEPOTI") (class "Default")
      (node (ref "IC2") (pin "34") (pinfunction "(ADC3)PA3_34") (pintype "bidirectional"))
      (node (ref "R27") (pin "1") (pinfunction "1_1") (pintype "passive"))
      (node (ref "R28") (pin "2") (pinfunction "2_2") (pintype "passive"))
    )
    (net (code "70") (name "VOUT") (class "Default")
      (node (ref "C18") (pin "+") (pinfunction "+_+") (pintype "passive"))
      (node (ref "C19") (pin "+") (pinfunction "+_+") (pintype "passive"))
      (node (ref "C20") (pin "1") (pinfunction "1_1") (pintype "passive"))
      (node (ref "C29") (pin "1") (pinfunction "1_1") (pintype "passive"))
      (node (ref "D4") (pin "C") (pinfunction "C_C") (pintype "passive"))
      (node (ref "D5") (pin "A") (pinfunction "A_A") (pintype "passive"))
      (node (ref "IC6") (pin "7") (pinfunction "VOUT_7") (pintype "power_in"))
      (node (ref "R34") (pin "2") (pinfunction "2_2") (pintype "passive"))
    )
    (net (code "71") (name "WD_MODE") (class "Default")
      (node (ref "IC1") (pin "3") (pinfunction "MODE_3") (pintype "bidirectional"))
      (node (ref "IC2") (pin "9") (pinfunction "(RXD)PD0_9") (pintype "bidirectional"))
      (node (ref "R3") (pin "1") (pinfunction "1_1") (pintype "passive"))
    )
    (net (code "72") (name "WD_TRIGGER") (class "Default")
      (node (ref "IC1") (pin "2") (pinfunction "TRIGGER_2") (pintype "bidirectional"))
      (node (ref "IC2") (pin "15") (pinfunction "(ICP)PD6_15") (pintype "bidirectional"))
      (node (ref "R4") (pin "1") (pinfunction "1_1") (pintype "passive"))
    )
    (net (code "73") (name "unconnected-(IC1-ENA-Pad4)") (class "Default")
      (node (ref "IC1") (pin "4") (pinfunction "ENA_4") (pintype "bidirectional"))
    )
    (net (code "74") (name "unconnected-(IC5-NC1-Pad1)") (class "Default")
      (node (ref "IC5") (pin "1") (pinfunction "NC1_1") (pintype "no_connect"))
    )
    (net (code "75") (name "unconnected-(IC5-NC2-Pad8)") (class "Default")
      (node (ref "IC5") (pin "8") (pinfunction "NC2_8") (pintype "no_connect"))
    )
    (net (code "76") (name "unconnected-(IC6-PGOOD-Pad6)") (class "Default")
      (node (ref "IC6") (pin "6") (pinfunction "PGOOD_6") (pintype "output"))
    )
    (net (code "77") (name "unconnected-(S1-S-Pad3)") (class "Default")
      (node (ref "S1") (pin "3") (pinfunction "S_3") (pintype "passive"))
    )
    (net (code "78") (name "unconnected-(X1H-S-Pad7)") (class "Default")
      (node (ref "X1") (pin "7") (pinfunction "S_7") (pintype "passive"))
    )
    (net (code "79") (name "unconnected-(X1I-S-Pad8)") (class "Default")
      (node (ref "X1") (pin "8") (pinfunction "S_8") (pintype "passive"))
    )
    (net (code "80") (name "{slash}RESET&WATCHDOG") (class "Default")
      (node (ref "IC2") (pin "4") (pinfunction "RESET_4") (pintype "input"))
      (node (ref "R1") (pin "1") (pinfunction "1_1") (pintype "passive"))
      (node (ref "R5") (pin "2") (pinfunction "2_2") (pintype "passive"))
    )
  )
)
